# SparkFun_QRE1113_Line_Sensor_Breakout_Di.net
KiCad netlist of a schematic drawn in EAGLE
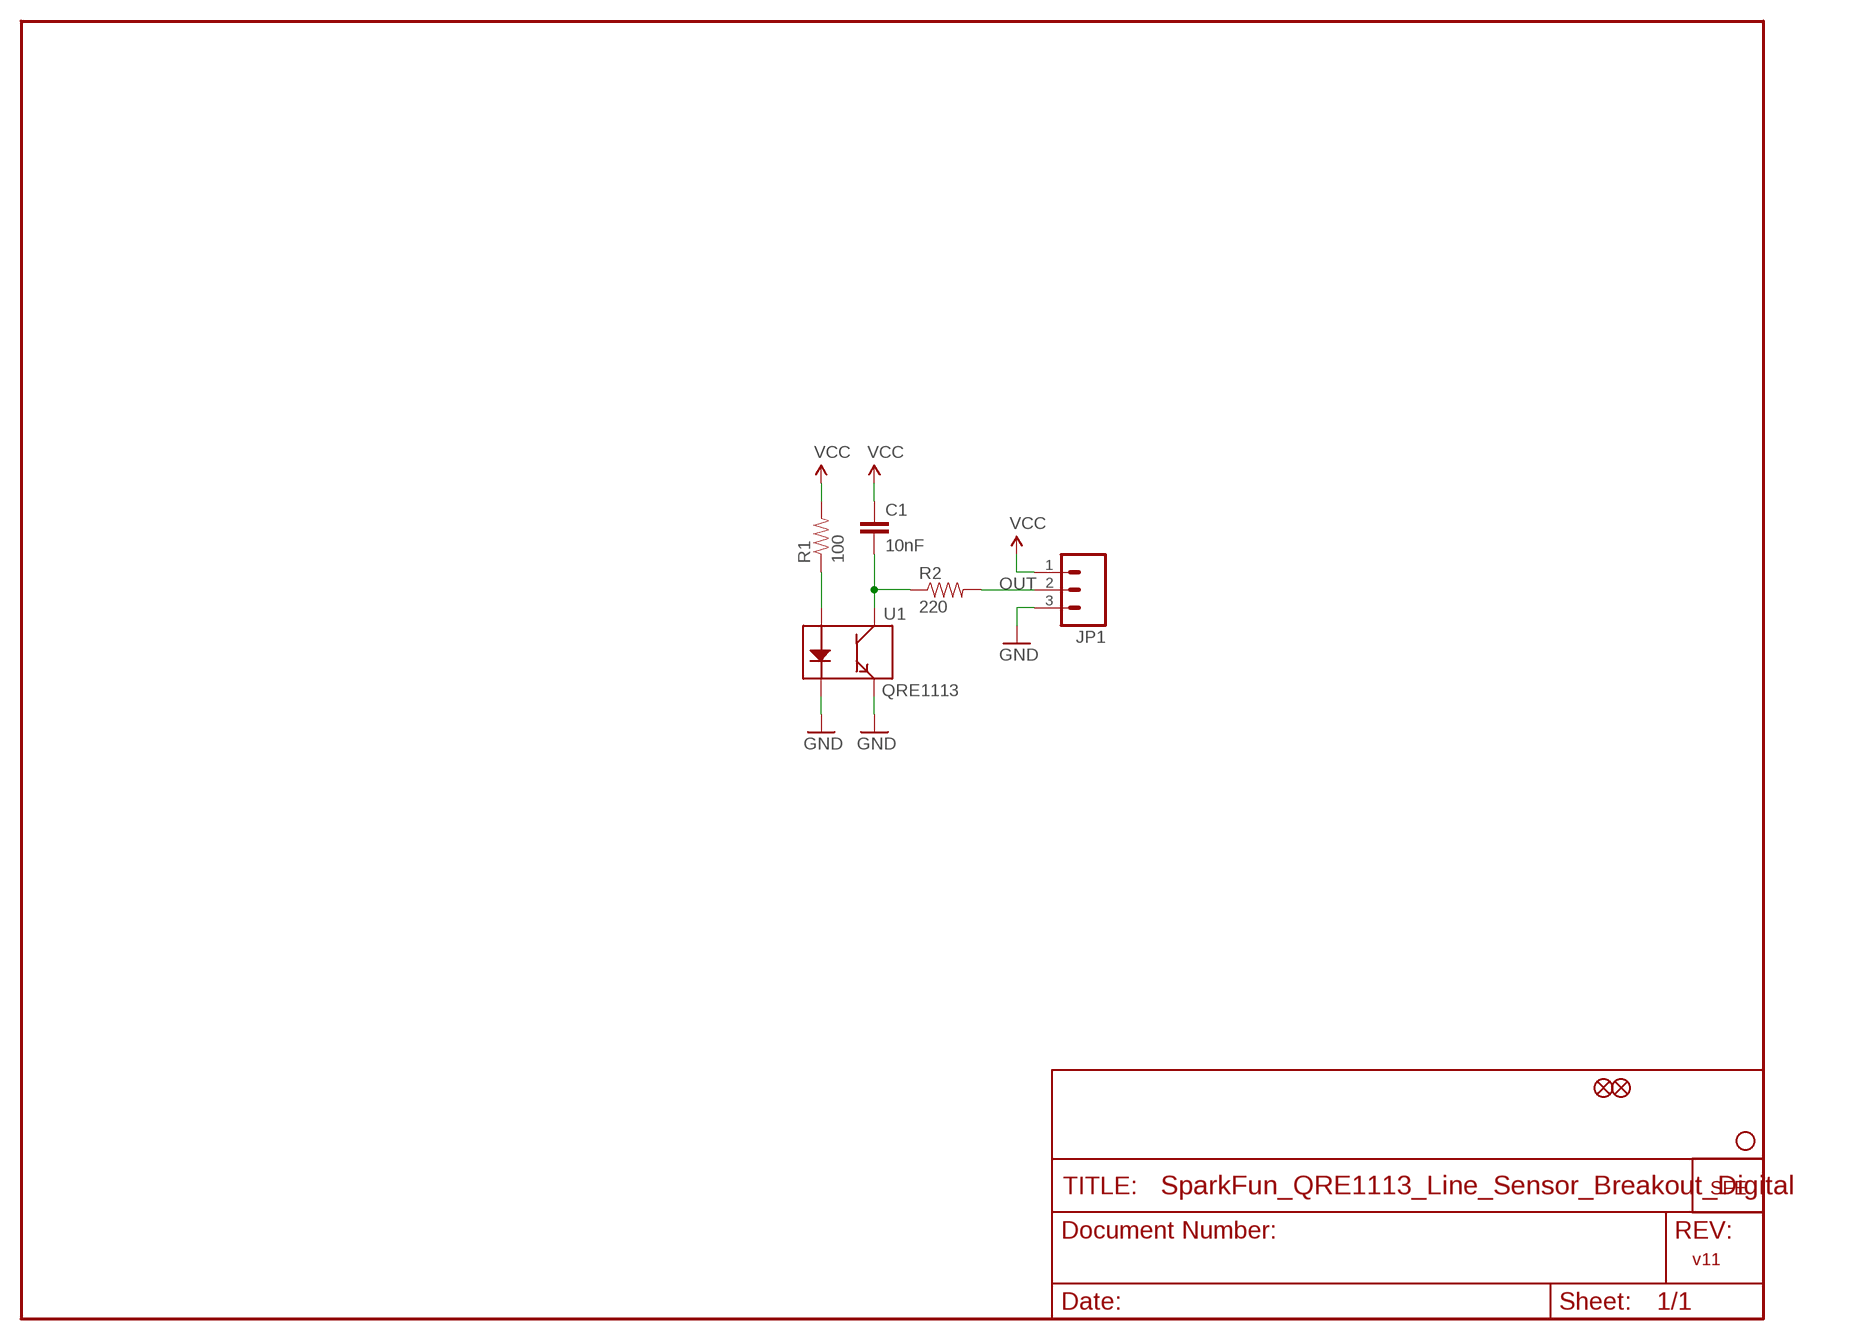
[diagram p0: schematic, sheet 1]

(export (version "E")
  (design (tool "Eeschema 10.0.6"))
  (components
    (comp (ref "C1")
      (value "10nF")
      (footprint "eagle-import:0402-CAP")
      (libsource (lib "eagle-import") (part "CAP0402-CAP"))
    )
    (comp (ref "FID1")
      (value "FIDUCIALUFIDUCIAL")
      (footprint "eagle-import:MICRO-FIDUCIAL")
      (libsource (lib "eagle-import") (part "FIDUCIALUFIDUCIAL"))
    )
    (comp (ref "FID2")
      (value "FIDUCIALUFIDUCIAL")
      (footprint "eagle-import:MICRO-FIDUCIAL")
      (libsource (lib "eagle-import") (part "FIDUCIALUFIDUCIAL"))
    )
    (comp (ref "JP1")
      (value "M03PTH")
      (footprint "eagle-import:1X03")
      (libsource (lib "eagle-import") (part "M03PTH"))
    )
    (comp (ref "JP2")
      (value "LOGO-SFESK")
      (footprint "eagle-import:SFE-LOGO-FLAME")
      (libsource (lib "eagle-import") (part "LOGO-SFESK"))
    )
    (comp (ref "JP3")
      (value "STAND-OFF")
      (footprint "eagle-import:STAND-OFF")
      (libsource (lib "eagle-import") (part "STAND-OFF"))
    )
    (comp (ref "R1")
      (value "100")
      (footprint "eagle-import:0402-RES")
      (libsource (lib "eagle-import") (part "RESISTOR0402-RES"))
    )
    (comp (ref "R2")
      (value "220")
      (footprint "eagle-import:0402-RES")
      (libsource (lib "eagle-import") (part "RESISTOR0402-RES"))
    )
    (comp (ref "U1")
      (value "QRE1113")
      (footprint "eagle-import:QRE1113")
      (libsource (lib "eagle-import") (part "QRE1113"))
    )
  )
  (nets
    (net (code "1") (name "/OUT") (class "Default")
      (node (ref "JP1") (pin "2") (pinfunction "2_2") (pintype "passive"))
      (node (ref "R2") (pin "2") (pinfunction "2_2") (pintype "passive"))
    )
    (net (code "2") (name "GND") (class "Default")
      (node (ref "JP1") (pin "3") (pinfunction "3_3") (pintype "passive"))
      (node (ref "U1") (pin "2") (pinfunction "K_2") (pintype "bidirectional"))
      (node (ref "U1") (pin "4") (pinfunction "E_4") (pintype "bidirectional"))
    )
    (net (code "3") (name "Net-(U1-A)") (class "Default")
      (node (ref "R1") (pin "1") (pinfunction "1_1") (pintype "passive"))
      (node (ref "U1") (pin "1") (pinfunction "A_1") (pintype "bidirectional"))
    )
    (net (code "4") (name "Net-(U1-C)") (class "Default")
      (node (ref "C1") (pin "2") (pinfunction "2_2") (pintype "passive"))
      (node (ref "R2") (pin "1") (pinfunction "1_1") (pintype "passive"))
      (node (ref "U1") (pin "3") (pinfunction "C_3") (pintype "bidirectional"))
    )
    (net (code "5") (name "VCC") (class "Default")
      (node (ref "C1") (pin "1") (pinfunction "1_1") (pintype "passive"))
      (node (ref "JP1") (pin "1") (pinfunction "1_1") (pintype "passive"))
      (node (ref "R1") (pin "2") (pinfunction "2_2") (pintype "passive"))
    )
  )
)
